# RGBWW-002.net
KiCad netlist of a schematic drawn in EAGLE
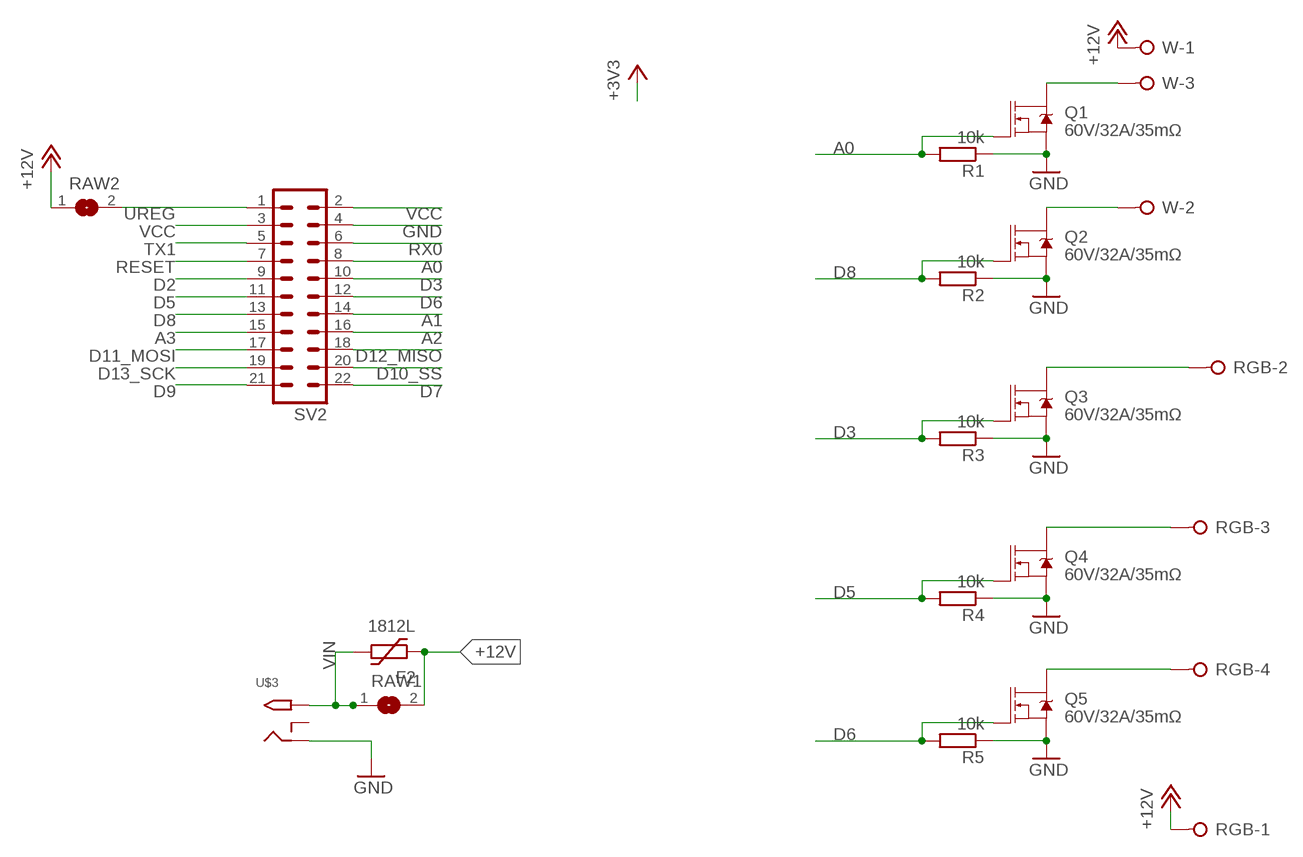
[diagram p0: schematic, sheet 1]

(export (version "E")
  (design (tool "Eeschema 10.0.6"))
  (components
    (comp (ref "F2")
      (value "1812L")
      (footprint "eagle-import:1812L")
      (libsource (lib "eagle-import") (part "1812L"))
    )
    (comp (ref "Q1")
      (value "60V/32A/35mΩ")
      (footprint "eagle-import:TO220V")
      (libsource (lib "eagle-import") (part "MOSFET-NCH-FQP30N06L"))
    )
    (comp (ref "Q2")
      (value "60V/32A/35mΩ")
      (footprint "eagle-import:TO220V")
      (libsource (lib "eagle-import") (part "MOSFET-NCH-FQP30N06L"))
    )
    (comp (ref "Q3")
      (value "60V/32A/35mΩ")
      (footprint "eagle-import:TO220V")
      (libsource (lib "eagle-import") (part "MOSFET-NCH-FQP30N06L"))
    )
    (comp (ref "Q4")
      (value "60V/32A/35mΩ")
      (footprint "eagle-import:TO220V")
      (libsource (lib "eagle-import") (part "MOSFET-NCH-FQP30N06L"))
    )
    (comp (ref "Q5")
      (value "60V/32A/35mΩ")
      (footprint "eagle-import:TO220V")
      (libsource (lib "eagle-import") (part "MOSFET-NCH-FQP30N06L"))
    )
    (comp (ref "R1")
      (value "10k")
      (footprint "eagle-import:R0805")
      (libsource (lib "eagle-import") (part "R-EU_R0805"))
    )
    (comp (ref "R2")
      (value "10k")
      (footprint "eagle-import:R0805")
      (libsource (lib "eagle-import") (part "R-EU_R0805"))
    )
    (comp (ref "R3")
      (value "10k")
      (footprint "eagle-import:R0805")
      (libsource (lib "eagle-import") (part "R-EU_R0805"))
    )
    (comp (ref "R4")
      (value "10k")
      (footprint "eagle-import:R0805")
      (libsource (lib "eagle-import") (part "R-EU_R0805"))
    )
    (comp (ref "R5")
      (value "10k")
      (footprint "eagle-import:R0805")
      (libsource (lib "eagle-import") (part "R-EU_R0805"))
    )
    (comp (ref "RAW1")
      (value "SJ")
      (footprint "eagle-import:SJ")
      (libsource (lib "eagle-import") (part "SJ"))
    )
    (comp (ref "RAW2")
      (value "SJ")
      (footprint "eagle-import:SJ")
      (libsource (lib "eagle-import") (part "SJ"))
    )
    (comp (ref "RGB")
      (value "W237-04P")
      (footprint "eagle-import:W237-4P")
      (libsource (lib "eagle-import") (part "W237-04P"))
    )
    (comp (ref "SV2")
      (value "MA11-2")
      (footprint "eagle-import:MA11-2")
      (libsource (lib "eagle-import") (part "MA11-2"))
    )
    (comp (ref "U$3")
      (value "2.1MMJACKTHM")
      (footprint "eagle-import:PJ-102A")
      (libsource (lib "eagle-import") (part "2.1MMJACKTHM"))
    )
    (comp (ref "W")
      (value "W237-03P")
      (footprint "eagle-import:W237-133")
      (libsource (lib "eagle-import") (part "W237-03P"))
    )
  )
  (nets
    (net (code "2") (name "+12V") (class "Default")
      (node (ref "F2") (pin "P$1") (pinfunction "1_P$1") (pintype "passive"))
      (node (ref "RAW1") (pin "2") (pinfunction "2_2") (pintype "passive"))
      (node (ref "RAW2") (pin "1") (pinfunction "1_1") (pintype "passive"))
      (node (ref "RGB") (pin "1") (pinfunction "KL_1") (pintype "passive"))
      (node (ref "W") (pin "1") (pinfunction "KL_1") (pintype "passive"))
    )
    (net (code "3") (name "/A0") (class "Default")
      (node (ref "Q1") (pin "1") (pinfunction "G_1") (pintype "bidirectional"))
      (node (ref "R1") (pin "2") (pinfunction "2_2") (pintype "passive"))
      (node (ref "SV2") (pin "8") (pinfunction "8_8") (pintype "passive"))
    )
    (net (code "4") (name "/A1") (class "Default")
      (node (ref "SV2") (pin "14") (pinfunction "14_14") (pintype "passive"))
    )
    (net (code "5") (name "/A2") (class "Default")
      (node (ref "SV2") (pin "16") (pinfunction "16_16") (pintype "passive"))
    )
    (net (code "6") (name "/A3") (class "Default")
      (node (ref "SV2") (pin "15") (pinfunction "15_15") (pintype "passive"))
    )
    (net (code "7") (name "/D2") (class "Default")
      (node (ref "SV2") (pin "9") (pinfunction "9_9") (pintype "passive"))
    )
    (net (code "8") (name "/D3") (class "Default")
      (node (ref "Q3") (pin "1") (pinfunction "G_1") (pintype "bidirectional"))
      (node (ref "R3") (pin "2") (pinfunction "2_2") (pintype "passive"))
      (node (ref "SV2") (pin "10") (pinfunction "10_10") (pintype "passive"))
    )
    (net (code "9") (name "/D5") (class "Default")
      (node (ref "Q4") (pin "1") (pinfunction "G_1") (pintype "bidirectional"))
      (node (ref "R4") (pin "2") (pinfunction "2_2") (pintype "passive"))
      (node (ref "SV2") (pin "11") (pinfunction "11_11") (pintype "passive"))
    )
    (net (code "10") (name "/D6") (class "Default")
      (node (ref "Q5") (pin "1") (pinfunction "G_1") (pintype "bidirectional"))
      (node (ref "R5") (pin "2") (pinfunction "2_2") (pintype "passive"))
      (node (ref "SV2") (pin "12") (pinfunction "12_12") (pintype "passive"))
    )
    (net (code "11") (name "/D7") (class "Default")
      (node (ref "SV2") (pin "22") (pinfunction "22_22") (pintype "passive"))
    )
    (net (code "12") (name "/D8") (class "Default")
      (node (ref "Q2") (pin "1") (pinfunction "G_1") (pintype "bidirectional"))
      (node (ref "R2") (pin "2") (pinfunction "2_2") (pintype "passive"))
      (node (ref "SV2") (pin "13") (pinfunction "13_13") (pintype "passive"))
    )
    (net (code "13") (name "/D9") (class "Default")
      (node (ref "SV2") (pin "21") (pinfunction "21_21") (pintype "passive"))
    )
    (net (code "14") (name "/D10_SS") (class "Default")
      (node (ref "SV2") (pin "20") (pinfunction "20_20") (pintype "passive"))
    )
    (net (code "15") (name "/D11_MOSI") (class "Default")
      (node (ref "SV2") (pin "17") (pinfunction "17_17") (pintype "passive"))
    )
    (net (code "16") (name "/D12_MISO") (class "Default")
      (node (ref "SV2") (pin "18") (pinfunction "18_18") (pintype "passive"))
    )
    (net (code "17") (name "/D13_SCK") (class "Default")
      (node (ref "SV2") (pin "19") (pinfunction "19_19") (pintype "passive"))
    )
    (net (code "18") (name "/RESET") (class "Default")
      (node (ref "SV2") (pin "7") (pinfunction "7_7") (pintype "passive"))
    )
    (net (code "19") (name "/RX0") (class "Default")
      (node (ref "SV2") (pin "6") (pinfunction "6_6") (pintype "passive"))
    )
    (net (code "20") (name "/TX1") (class "Default")
      (node (ref "SV2") (pin "5") (pinfunction "5_5") (pintype "passive"))
    )
    (net (code "21") (name "/UREG") (class "Default")
      (node (ref "RAW2") (pin "2") (pinfunction "2_2") (pintype "passive"))
      (node (ref "SV2") (pin "1") (pinfunction "1_1") (pintype "passive"))
    )
    (net (code "22") (name "/VCC") (class "Default")
      (node (ref "SV2") (pin "2") (pinfunction "2_2") (pintype "passive"))
      (node (ref "SV2") (pin "3") (pinfunction "3_3") (pintype "passive"))
    )
    (net (code "23") (name "/VIN") (class "Default")
      (node (ref "F2") (pin "P$2") (pinfunction "2_P$2") (pintype "passive"))
      (node (ref "RAW1") (pin "1") (pinfunction "1_1") (pintype "passive"))
      (node (ref "U$3") (pin "TIP") (pinfunction "TIP_TIP") (pintype "bidirectional"))
    )
    (net (code "24") (name "GND") (class "Default")
      (node (ref "Q1") (pin "3") (pinfunction "S_3") (pintype "bidirectional"))
      (node (ref "Q2") (pin "3") (pinfunction "S_3") (pintype "bidirectional"))
      (node (ref "Q3") (pin "3") (pinfunction "S_3") (pintype "bidirectional"))
      (node (ref "Q4") (pin "3") (pinfunction "S_3") (pintype "bidirectional"))
      (node (ref "Q5") (pin "3") (pinfunction "S_3") (pintype "bidirectional"))
      (node (ref "R1") (pin "1") (pinfunction "1_1") (pintype "passive"))
      (node (ref "R2") (pin "1") (pinfunction "1_1") (pintype "passive"))
      (node (ref "R3") (pin "1") (pinfunction "1_1") (pintype "passive"))
      (node (ref "R4") (pin "1") (pinfunction "1_1") (pintype "passive"))
      (node (ref "R5") (pin "1") (pinfunction "1_1") (pintype "passive"))
      (node (ref "SV2") (pin "4") (pinfunction "4_4") (pintype "passive"))
      (node (ref "U$3") (pin "RING") (pinfunction "RING_RING") (pintype "bidirectional"))
    )
    (net (code "25") (name "Net-(Q1-D)") (class "Default")
      (node (ref "Q1") (pin "2") (pinfunction "D_2") (pintype "bidirectional"))
      (node (ref "W") (pin "3") (pinfunction "KL_3") (pintype "passive"))
    )
    (net (code "26") (name "Net-(Q2-D)") (class "Default")
      (node (ref "Q2") (pin "2") (pinfunction "D_2") (pintype "bidirectional"))
      (node (ref "W") (pin "2") (pinfunction "KL_2") (pintype "passive"))
    )
    (net (code "27") (name "Net-(Q3-D)") (class "Default")
      (node (ref "Q3") (pin "2") (pinfunction "D_2") (pintype "bidirectional"))
      (node (ref "RGB") (pin "2") (pinfunction "KL_2") (pintype "passive"))
    )
    (net (code "28") (name "Net-(Q4-D)") (class "Default")
      (node (ref "Q4") (pin "2") (pinfunction "D_2") (pintype "bidirectional"))
      (node (ref "RGB") (pin "3") (pinfunction "KL_3") (pintype "passive"))
    )
    (net (code "29") (name "Net-(Q5-D)") (class "Default")
      (node (ref "Q5") (pin "2") (pinfunction "D_2") (pintype "bidirectional"))
      (node (ref "RGB") (pin "4") (pinfunction "KL_4") (pintype "passive"))
    )
    (net (code "30") (name "unconnected-(U$3-PadRING_SW)") (class "Default")
      (node (ref "U$3") (pin "RING_SW") (pinfunction "RING_SW_RING_SW") (pintype "bidirectional"))
    )
  )
)
